# IOIO.net
KiCad netlist of a schematic drawn in EAGLE
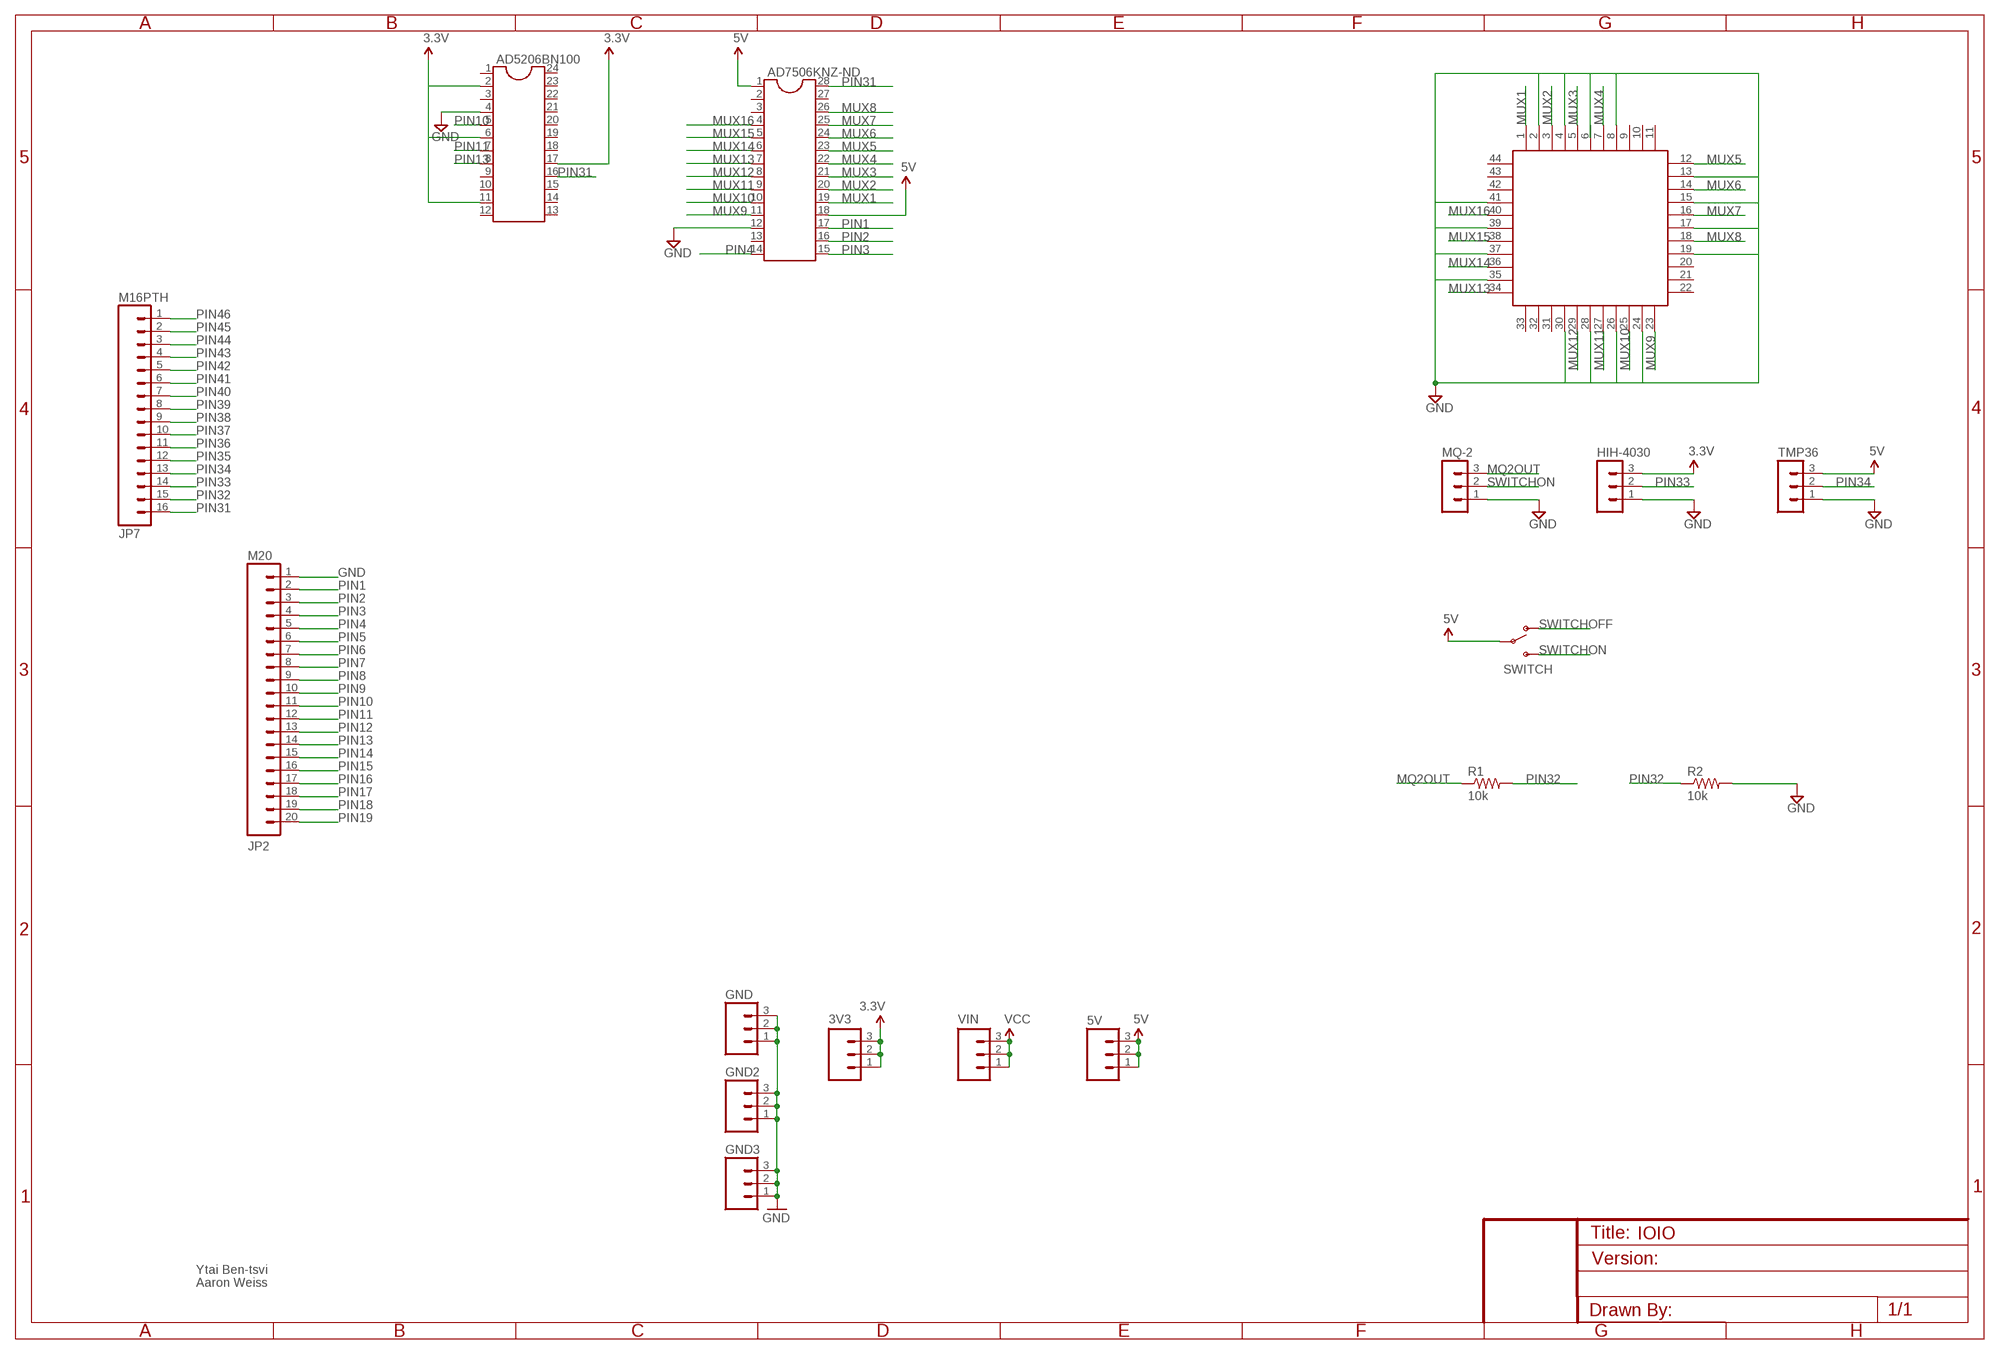
[diagram p0: schematic, sheet 1]

(export (version "E")
  (design (tool "Eeschema 10.0.6"))
  (components
    (comp (ref "3V3")
      (value "M03PTH")
      (footprint "eagle-import:1X03")
      (libsource (lib "eagle-import") (part "M03PTH"))
    )
    (comp (ref "5V")
      (value "M03PTH")
      (footprint "eagle-import:1X03")
      (libsource (lib "eagle-import") (part "M03PTH"))
    )
    (comp (ref "AD5206BN100")
      (value "DIL24-3")
      (footprint "eagle-import:DIL24-3")
      (libsource (lib "eagle-import") (part "DIL24-3"))
    )
    (comp (ref "AD7506KNZ-ND")
      (value "DIL28")
      (footprint "eagle-import:DIL28-6")
      (libsource (lib "eagle-import") (part "DIL28"))
    )
    (comp (ref "GND")
      (value "M03PTH")
      (footprint "eagle-import:1X03")
      (libsource (lib "eagle-import") (part "M03PTH"))
    )
    (comp (ref "GND2")
      (value "M03PTH")
      (footprint "eagle-import:1X03")
      (libsource (lib "eagle-import") (part "M03PTH"))
    )
    (comp (ref "GND3")
      (value "M03PTH")
      (footprint "eagle-import:1X03")
      (libsource (lib "eagle-import") (part "M03PTH"))
    )
    (comp (ref "HIH-4030")
      (value "MA03-1")
      (footprint "eagle-import:MA03-1")
      (libsource (lib "eagle-import") (part "MA03-1"))
    )
    (comp (ref "JP2")
      (value "M20")
      (footprint "eagle-import:1X20")
      (libsource (lib "eagle-import") (part "M20"))
    )
    (comp (ref "JP7")
      (value "M16PTH")
      (footprint "eagle-import:1X16")
      (libsource (lib "eagle-import") (part "M16PTH"))
    )
    (comp (ref "MQ-2")
      (value "MA03-1")
      (footprint "eagle-import:MA03-1")
      (libsource (lib "eagle-import") (part "MA03-1"))
    )
    (comp (ref "R1")
      (value "10k")
      (footprint "eagle-import:0207_7")
      (libsource (lib "eagle-import") (part "R-US_0207/7"))
    )
    (comp (ref "R2")
      (value "10k")
      (footprint "eagle-import:0207_7")
      (libsource (lib "eagle-import") (part "R-US_0207/7"))
    )
    (comp (ref "SWITCH")
      (value "SWITCH-SPSTPTH")
      (footprint "eagle-import:SWITCH-SPDT")
      (libsource (lib "eagle-import") (part "SWITCH-SPSTPTH"))
    )
    (comp (ref "TMP36")
      (value "MA03-1")
      (footprint "eagle-import:MA03-1")
      (libsource (lib "eagle-import") (part "MA03-1"))
    )
    (comp (ref "U$1")
      (value "S44")
      (footprint "eagle-import:S44")
      (libsource (lib "eagle-import") (part "S44"))
    )
    (comp (ref "VIN")
      (value "M03PTH")
      (footprint "eagle-import:1X03")
      (libsource (lib "eagle-import") (part "M03PTH"))
    )
  )
  (nets
    (net (code "1") (name "/MQ2OUT") (class "Default")
      (node (ref "MQ-2") (pin "3") (pinfunction "3_3") (pintype "passive"))
      (node (ref "R1") (pin "1") (pinfunction "1_1") (pintype "passive"))
    )
    (net (code "2") (name "/MUX1") (class "Default")
      (node (ref "AD7506KNZ-ND") (pin "19") (pinfunction "19_19") (pintype "passive"))
      (node (ref "U$1") (pin "1") (pinfunction "P$1_1") (pintype "bidirectional"))
    )
    (net (code "3") (name "/MUX2") (class "Default")
      (node (ref "AD7506KNZ-ND") (pin "20") (pinfunction "20_20") (pintype "passive"))
      (node (ref "U$1") (pin "3") (pinfunction "P$3_3") (pintype "bidirectional"))
    )
    (net (code "4") (name "/MUX3") (class "Default")
      (node (ref "AD7506KNZ-ND") (pin "21") (pinfunction "21_21") (pintype "passive"))
      (node (ref "U$1") (pin "5") (pinfunction "P$5_5") (pintype "bidirectional"))
    )
    (net (code "5") (name "/MUX4") (class "Default")
      (node (ref "AD7506KNZ-ND") (pin "22") (pinfunction "22_22") (pintype "passive"))
      (node (ref "U$1") (pin "7") (pinfunction "P$7_7") (pintype "bidirectional"))
    )
    (net (code "6") (name "/MUX5") (class "Default")
      (node (ref "AD7506KNZ-ND") (pin "23") (pinfunction "23_23") (pintype "passive"))
      (node (ref "U$1") (pin "12") (pinfunction "P$12_12") (pintype "bidirectional"))
    )
    (net (code "7") (name "/MUX6") (class "Default")
      (node (ref "AD7506KNZ-ND") (pin "24") (pinfunction "24_24") (pintype "passive"))
      (node (ref "U$1") (pin "14") (pinfunction "P$14_14") (pintype "bidirectional"))
    )
    (net (code "8") (name "/MUX7") (class "Default")
      (node (ref "AD7506KNZ-ND") (pin "25") (pinfunction "25_25") (pintype "passive"))
      (node (ref "U$1") (pin "16") (pinfunction "P$16_16") (pintype "bidirectional"))
    )
    (net (code "9") (name "/MUX8") (class "Default")
      (node (ref "AD7506KNZ-ND") (pin "26") (pinfunction "26_26") (pintype "passive"))
      (node (ref "U$1") (pin "18") (pinfunction "P$18_18") (pintype "bidirectional"))
    )
    (net (code "10") (name "/MUX9") (class "Default")
      (node (ref "AD7506KNZ-ND") (pin "11") (pinfunction "11_11") (pintype "passive"))
      (node (ref "U$1") (pin "23") (pinfunction "P$23_23") (pintype "bidirectional"))
    )
    (net (code "11") (name "/MUX10") (class "Default")
      (node (ref "AD7506KNZ-ND") (pin "10") (pinfunction "10_10") (pintype "passive"))
      (node (ref "U$1") (pin "25") (pinfunction "P$25_25") (pintype "bidirectional"))
    )
    (net (code "12") (name "/MUX11") (class "Default")
      (node (ref "AD7506KNZ-ND") (pin "9") (pinfunction "9_9") (pintype "passive"))
      (node (ref "U$1") (pin "27") (pinfunction "P$27_27") (pintype "bidirectional"))
    )
    (net (code "13") (name "/MUX12") (class "Default")
      (node (ref "AD7506KNZ-ND") (pin "8") (pinfunction "8_8") (pintype "passive"))
      (node (ref "U$1") (pin "29") (pinfunction "P$29_29") (pintype "bidirectional"))
    )
    (net (code "14") (name "/MUX13") (class "Default")
      (node (ref "AD7506KNZ-ND") (pin "7") (pinfunction "7_7") (pintype "passive"))
      (node (ref "U$1") (pin "34") (pinfunction "P$34_34") (pintype "bidirectional"))
    )
    (net (code "15") (name "/MUX14") (class "Default")
      (node (ref "AD7506KNZ-ND") (pin "6") (pinfunction "6_6") (pintype "passive"))
      (node (ref "U$1") (pin "36") (pinfunction "P$36_36") (pintype "bidirectional"))
    )
    (net (code "16") (name "/MUX15") (class "Default")
      (node (ref "AD7506KNZ-ND") (pin "5") (pinfunction "5_5") (pintype "passive"))
      (node (ref "U$1") (pin "38") (pinfunction "P$38_38") (pintype "bidirectional"))
    )
    (net (code "17") (name "/MUX16") (class "Default")
      (node (ref "AD7506KNZ-ND") (pin "4") (pinfunction "4_4") (pintype "passive"))
      (node (ref "U$1") (pin "40") (pinfunction "P$40_40") (pintype "bidirectional"))
    )
    (net (code "18") (name "/PIN1") (class "Default")
      (node (ref "AD7506KNZ-ND") (pin "17") (pinfunction "17_17") (pintype "passive"))
      (node (ref "JP2") (pin "2") (pinfunction "2_2") (pintype "passive"))
    )
    (net (code "19") (name "/PIN2") (class "Default")
      (node (ref "AD7506KNZ-ND") (pin "16") (pinfunction "16_16") (pintype "passive"))
      (node (ref "JP2") (pin "3") (pinfunction "3_3") (pintype "passive"))
    )
    (net (code "20") (name "/PIN3") (class "Default")
      (node (ref "AD7506KNZ-ND") (pin "15") (pinfunction "15_15") (pintype "passive"))
      (node (ref "JP2") (pin "4") (pinfunction "4_4") (pintype "passive"))
    )
    (net (code "21") (name "/PIN4") (class "Default")
      (node (ref "AD7506KNZ-ND") (pin "14") (pinfunction "14_14") (pintype "passive"))
      (node (ref "JP2") (pin "5") (pinfunction "5_5") (pintype "passive"))
    )
    (net (code "22") (name "/PIN5") (class "Default")
      (node (ref "JP2") (pin "6") (pinfunction "6_6") (pintype "passive"))
    )
    (net (code "23") (name "/PIN6") (class "Default")
      (node (ref "JP2") (pin "7") (pinfunction "7_7") (pintype "passive"))
    )
    (net (code "24") (name "/PIN7") (class "Default")
      (node (ref "JP2") (pin "8") (pinfunction "8_8") (pintype "passive"))
    )
    (net (code "25") (name "/PIN8") (class "Default")
      (node (ref "JP2") (pin "9") (pinfunction "9_9") (pintype "passive"))
    )
    (net (code "26") (name "/PIN9") (class "Default")
      (node (ref "JP2") (pin "10") (pinfunction "10_10") (pintype "passive"))
    )
    (net (code "27") (name "/PIN10") (class "Default")
      (node (ref "AD5206BN100") (pin "5") (pinfunction "5_5") (pintype "passive"))
      (node (ref "JP2") (pin "11") (pinfunction "11_11") (pintype "passive"))
    )
    (net (code "28") (name "/PIN11") (class "Default")
      (node (ref "AD5206BN100") (pin "7") (pinfunction "7_7") (pintype "passive"))
      (node (ref "JP2") (pin "12") (pinfunction "12_12") (pintype "passive"))
    )
    (net (code "29") (name "/PIN12") (class "Default")
      (node (ref "JP2") (pin "13") (pinfunction "13_13") (pintype "passive"))
    )
    (net (code "30") (name "/PIN13") (class "Default")
      (node (ref "AD5206BN100") (pin "8") (pinfunction "8_8") (pintype "passive"))
      (node (ref "JP2") (pin "14") (pinfunction "14_14") (pintype "passive"))
    )
    (net (code "31") (name "/PIN14") (class "Default")
      (node (ref "JP2") (pin "15") (pinfunction "15_15") (pintype "passive"))
    )
    (net (code "32") (name "/PIN15") (class "Default")
      (node (ref "JP2") (pin "16") (pinfunction "16_16") (pintype "passive"))
    )
    (net (code "33") (name "/PIN16") (class "Default")
      (node (ref "JP2") (pin "17") (pinfunction "17_17") (pintype "passive"))
    )
    (net (code "34") (name "/PIN17") (class "Default")
      (node (ref "JP2") (pin "18") (pinfunction "18_18") (pintype "passive"))
    )
    (net (code "35") (name "/PIN18") (class "Default")
      (node (ref "JP2") (pin "19") (pinfunction "19_19") (pintype "passive"))
    )
    (net (code "36") (name "/PIN19") (class "Default")
      (node (ref "JP2") (pin "20") (pinfunction "20_20") (pintype "passive"))
    )
    (net (code "37") (name "/PIN31") (class "Default")
      (node (ref "AD5206BN100") (pin "16") (pinfunction "16_16") (pintype "passive"))
      (node (ref "AD7506KNZ-ND") (pin "28") (pinfunction "28_28") (pintype "passive"))
      (node (ref "JP7") (pin "16") (pinfunction "16_16") (pintype "passive"))
    )
    (net (code "38") (name "/PIN32") (class "Default")
      (node (ref "JP7") (pin "15") (pinfunction "15_15") (pintype "passive"))
      (node (ref "R1") (pin "2") (pinfunction "2_2") (pintype "passive"))
      (node (ref "R2") (pin "1") (pinfunction "1_1") (pintype "passive"))
    )
    (net (code "39") (name "/PIN33") (class "Default")
      (node (ref "HIH-4030") (pin "2") (pinfunction "2_2") (pintype "passive"))
      (node (ref "JP7") (pin "14") (pinfunction "14_14") (pintype "passive"))
    )
    (net (code "40") (name "/PIN34") (class "Default")
      (node (ref "JP7") (pin "13") (pinfunction "13_13") (pintype "passive"))
      (node (ref "TMP36") (pin "2") (pinfunction "2_2") (pintype "passive"))
    )
    (net (code "41") (name "/PIN35") (class "Default")
      (node (ref "JP7") (pin "12") (pinfunction "12_12") (pintype "passive"))
    )
    (net (code "42") (name "/PIN36") (class "Default")
      (node (ref "JP7") (pin "11") (pinfunction "11_11") (pintype "passive"))
    )
    (net (code "43") (name "/PIN37") (class "Default")
      (node (ref "JP7") (pin "10") (pinfunction "10_10") (pintype "passive"))
    )
    (net (code "44") (name "/PIN38") (class "Default")
      (node (ref "JP7") (pin "9") (pinfunction "9_9") (pintype "passive"))
    )
    (net (code "45") (name "/PIN39") (class "Default")
      (node (ref "JP7") (pin "8") (pinfunction "8_8") (pintype "passive"))
    )
    (net (code "46") (name "/PIN40") (class "Default")
      (node (ref "JP7") (pin "7") (pinfunction "7_7") (pintype "passive"))
    )
    (net (code "47") (name "/PIN41") (class "Default")
      (node (ref "JP7") (pin "6") (pinfunction "6_6") (pintype "passive"))
    )
    (net (code "48") (name "/PIN42") (class "Default")
      (node (ref "JP7") (pin "5") (pinfunction "5_5") (pintype "passive"))
    )
    (net (code "49") (name "/PIN43") (class "Default")
      (node (ref "JP7") (pin "4") (pinfunction "4_4") (pintype "passive"))
    )
    (net (code "50") (name "/PIN44") (class "Default")
      (node (ref "JP7") (pin "3") (pinfunction "3_3") (pintype "passive"))
    )
    (net (code "51") (name "/PIN45") (class "Default")
      (node (ref "JP7") (pin "2") (pinfunction "2_2") (pintype "passive"))
    )
    (net (code "52") (name "/PIN46") (class "Default")
      (node (ref "JP7") (pin "1") (pinfunction "1_1") (pintype "passive"))
    )
    (net (code "53") (name "/SWITCHOFF") (class "Default")
      (node (ref "SWITCH") (pin "1") (pinfunction "O_1") (pintype "passive"))
    )
    (net (code "54") (name "/SWITCHON") (class "Default")
      (node (ref "MQ-2") (pin "2") (pinfunction "2_2") (pintype "passive"))
      (node (ref "SWITCH") (pin "3") (pinfunction "S_3") (pintype "passive"))
    )
    (net (code "55") (name "3.3V") (class "Default")
      (node (ref "3V3") (pin "1") (pinfunction "1_1") (pintype "passive"))
      (node (ref "3V3") (pin "2") (pinfunction "2_2") (pintype "passive"))
      (node (ref "3V3") (pin "3") (pinfunction "3_3") (pintype "passive"))
      (node (ref "AD5206BN100") (pin "11") (pinfunction "11_11") (pintype "passive"))
      (node (ref "AD5206BN100") (pin "17") (pinfunction "17_17") (pintype "passive"))
      (node (ref "AD5206BN100") (pin "2") (pinfunction "2_2") (pintype "passive"))
      (node (ref "AD5206BN100") (pin "6") (pinfunction "6_6") (pintype "passive"))
      (node (ref "HIH-4030") (pin "3") (pinfunction "3_3") (pintype "passive"))
    )
    (net (code "56") (name "5V") (class "Default")
      (node (ref "5V") (pin "1") (pinfunction "1_1") (pintype "passive"))
      (node (ref "5V") (pin "2") (pinfunction "2_2") (pintype "passive"))
      (node (ref "5V") (pin "3") (pinfunction "3_3") (pintype "passive"))
      (node (ref "AD7506KNZ-ND") (pin "1") (pinfunction "1_1") (pintype "passive"))
      (node (ref "AD7506KNZ-ND") (pin "18") (pinfunction "18_18") (pintype "passive"))
      (node (ref "SWITCH") (pin "2") (pinfunction "P_2") (pintype "passive"))
      (node (ref "TMP36") (pin "3") (pinfunction "3_3") (pintype "passive"))
    )
    (net (code "57") (name "GND") (class "Default")
      (node (ref "AD5206BN100") (pin "4") (pinfunction "4_4") (pintype "passive"))
      (node (ref "AD7506KNZ-ND") (pin "12") (pinfunction "12_12") (pintype "passive"))
      (node (ref "GND") (pin "1") (pinfunction "1_1") (pintype "passive"))
      (node (ref "GND") (pin "2") (pinfunction "2_2") (pintype "passive"))
      (node (ref "GND") (pin "3") (pinfunction "3_3") (pintype "passive"))
      (node (ref "GND2") (pin "1") (pinfunction "1_1") (pintype "passive"))
      (node (ref "GND2") (pin "2") (pinfunction "2_2") (pintype "passive"))
      (node (ref "GND2") (pin "3") (pinfunction "3_3") (pintype "passive"))
      (node (ref "GND3") (pin "1") (pinfunction "1_1") (pintype "passive"))
      (node (ref "GND3") (pin "2") (pinfunction "2_2") (pintype "passive"))
      (node (ref "GND3") (pin "3") (pinfunction "3_3") (pintype "passive"))
      (node (ref "HIH-4030") (pin "1") (pinfunction "1_1") (pintype "passive"))
      (node (ref "JP2") (pin "1") (pinfunction "1_1") (pintype "passive"))
      (node (ref "MQ-2") (pin "1") (pinfunction "1_1") (pintype "passive"))
      (node (ref "R2") (pin "2") (pinfunction "2_2") (pintype "passive"))
      (node (ref "TMP36") (pin "1") (pinfunction "1_1") (pintype "passive"))
      (node (ref "U$1") (pin "13") (pinfunction "P$13_13") (pintype "bidirectional"))
      (node (ref "U$1") (pin "15") (pinfunction "P$15_15") (pintype "bidirectional"))
      (node (ref "U$1") (pin "17") (pinfunction "P$17_17") (pintype "bidirectional"))
      (node (ref "U$1") (pin "19") (pinfunction "P$19_19") (pintype "bidirectional"))
      (node (ref "U$1") (pin "2") (pinfunction "P$2_2") (pintype "bidirectional"))
      (node (ref "U$1") (pin "24") (pinfunction "P$24_24") (pintype "bidirectional"))
      (node (ref "U$1") (pin "26") (pinfunction "P$26_26") (pintype "bidirectional"))
      (node (ref "U$1") (pin "28") (pinfunction "P$28_28") (pintype "bidirectional"))
      (node (ref "U$1") (pin "30") (pinfunction "P$30_30") (pintype "bidirectional"))
      (node (ref "U$1") (pin "35") (pinfunction "P$35_35") (pintype "bidirectional"))
      (node (ref "U$1") (pin "37") (pinfunction "P$37_37") (pintype "bidirectional"))
      (node (ref "U$1") (pin "39") (pinfunction "P$39_39") (pintype "bidirectional"))
      (node (ref "U$1") (pin "4") (pinfunction "P$4_4") (pintype "bidirectional"))
      (node (ref "U$1") (pin "41") (pinfunction "P$41_41") (pintype "bidirectional"))
      (node (ref "U$1") (pin "8") (pinfunction "P$8_8") (pintype "bidirectional"))
    )
    (net (code "58") (name "VCC") (class "Default")
      (node (ref "VIN") (pin "1") (pinfunction "1_1") (pintype "passive"))
      (node (ref "VIN") (pin "2") (pinfunction "2_2") (pintype "passive"))
      (node (ref "VIN") (pin "3") (pinfunction "3_3") (pintype "passive"))
    )
    (net (code "59") (name "unconnected-(AD5206BN100-Pad1)") (class "Default")
      (node (ref "AD5206BN100") (pin "1") (pinfunction "1_1") (pintype "passive"))
    )
    (net (code "60") (name "unconnected-(AD5206BN100-Pad3)") (class "Default")
      (node (ref "AD5206BN100") (pin "3") (pinfunction "3_3") (pintype "passive"))
    )
    (net (code "61") (name "unconnected-(AD5206BN100-Pad9)") (class "Default")
      (node (ref "AD5206BN100") (pin "9") (pinfunction "9_9") (pintype "passive"))
    )
    (net (code "62") (name "unconnected-(AD5206BN100-Pad10)") (class "Default")
      (node (ref "AD5206BN100") (pin "10") (pinfunction "10_10") (pintype "passive"))
    )
    (net (code "63") (name "unconnected-(AD5206BN100-Pad12)") (class "Default")
      (node (ref "AD5206BN100") (pin "12") (pinfunction "12_12") (pintype "passive"))
    )
    (net (code "64") (name "unconnected-(AD5206BN100-Pad13)") (class "Default")
      (node (ref "AD5206BN100") (pin "13") (pinfunction "13_13") (pintype "passive"))
    )
    (net (code "65") (name "unconnected-(AD5206BN100-Pad14)") (class "Default")
      (node (ref "AD5206BN100") (pin "14") (pinfunction "14_14") (pintype "passive"))
    )
    (net (code "66") (name "unconnected-(AD5206BN100-Pad15)") (class "Default")
      (node (ref "AD5206BN100") (pin "15") (pinfunction "15_15") (pintype "passive"))
    )
    (net (code "67") (name "unconnected-(AD5206BN100-Pad18)") (class "Default")
      (node (ref "AD5206BN100") (pin "18") (pinfunction "18_18") (pintype "passive"))
    )
    (net (code "68") (name "unconnected-(AD5206BN100-Pad19)") (class "Default")
      (node (ref "AD5206BN100") (pin "19") (pinfunction "19_19") (pintype "passive"))
    )
    (net (code "69") (name "unconnected-(AD5206BN100-Pad20)") (class "Default")
      (node (ref "AD5206BN100") (pin "20") (pinfunction "20_20") (pintype "passive"))
    )
    (net (code "70") (name "unconnected-(AD5206BN100-Pad21)") (class "Default")
      (node (ref "AD5206BN100") (pin "21") (pinfunction "21_21") (pintype "passive"))
    )
    (net (code "71") (name "unconnected-(AD5206BN100-Pad22)") (class "Default")
      (node (ref "AD5206BN100") (pin "22") (pinfunction "22_22") (pintype "passive"))
    )
    (net (code "72") (name "unconnected-(AD5206BN100-Pad23)") (class "Default")
      (node (ref "AD5206BN100") (pin "23") (pinfunction "23_23") (pintype "passive"))
    )
    (net (code "73") (name "unconnected-(AD5206BN100-Pad24)") (class "Default")
      (node (ref "AD5206BN100") (pin "24") (pinfunction "24_24") (pintype "passive"))
    )
    (net (code "74") (name "unconnected-(AD7506KNZ-ND-Pad2)") (class "Default")
      (node (ref "AD7506KNZ-ND") (pin "2") (pinfunction "2_2") (pintype "passive"))
    )
    (net (code "75") (name "unconnected-(AD7506KNZ-ND-Pad3)") (class "Default")
      (node (ref "AD7506KNZ-ND") (pin "3") (pinfunction "3_3") (pintype "passive"))
    )
    (net (code "76") (name "unconnected-(AD7506KNZ-ND-Pad13)") (class "Default")
      (node (ref "AD7506KNZ-ND") (pin "13") (pinfunction "13_13") (pintype "passive"))
    )
    (net (code "77") (name "unconnected-(AD7506KNZ-ND-Pad27)") (class "Default")
      (node (ref "AD7506KNZ-ND") (pin "27") (pinfunction "27_27") (pintype "passive"))
    )
    (net (code "78") (name "unconnected-(U$1-P$6-Pad6)") (class "Default")
      (node (ref "U$1") (pin "6") (pinfunction "P$6_6") (pintype "bidirectional"))
    )
    (net (code "79") (name "unconnected-(U$1-P$9-Pad9)") (class "Default")
      (node (ref "U$1") (pin "9") (pinfunction "P$9_9") (pintype "bidirectional"))
    )
    (net (code "80") (name "unconnected-(U$1-P$10-Pad10)") (class "Default")
      (node (ref "U$1") (pin "10") (pinfunction "P$10_10") (pintype "bidirectional"))
    )
    (net (code "81") (name "unconnected-(U$1-P$11-Pad11)") (class "Default")
      (node (ref "U$1") (pin "11") (pinfunction "P$11_11") (pintype "bidirectional"))
    )
    (net (code "82") (name "unconnected-(U$1-P$20-Pad20)") (class "Default")
      (node (ref "U$1") (pin "20") (pinfunction "P$20_20") (pintype "bidirectional"))
    )
    (net (code "83") (name "unconnected-(U$1-P$21-Pad21)") (class "Default")
      (node (ref "U$1") (pin "21") (pinfunction "P$21_21") (pintype "bidirectional"))
    )
    (net (code "84") (name "unconnected-(U$1-P$22-Pad22)") (class "Default")
      (node (ref "U$1") (pin "22") (pinfunction "P$22_22") (pintype "bidirectional"))
    )
    (net (code "85") (name "unconnected-(U$1-P$31-Pad31)") (class "Default")
      (node (ref "U$1") (pin "31") (pinfunction "P$31_31") (pintype "bidirectional"))
    )
    (net (code "86") (name "unconnected-(U$1-P$32-Pad32)") (class "Default")
      (node (ref "U$1") (pin "32") (pinfunction "P$32_32") (pintype "bidirectional"))
    )
    (net (code "87") (name "unconnected-(U$1-P$33-Pad33)") (class "Default")
      (node (ref "U$1") (pin "33") (pinfunction "P$33_33") (pintype "bidirectional"))
    )
    (net (code "88") (name "unconnected-(U$1-P$42-Pad42)") (class "Default")
      (node (ref "U$1") (pin "42") (pinfunction "P$42_42") (pintype "bidirectional"))
    )
    (net (code "89") (name "unconnected-(U$1-P$43-Pad43)") (class "Default")
      (node (ref "U$1") (pin "43") (pinfunction "P$43_43") (pintype "bidirectional"))
    )
    (net (code "90") (name "unconnected-(U$1-P$44-Pad44)") (class "Default")
      (node (ref "U$1") (pin "44") (pinfunction "P$44_44") (pintype "bidirectional"))
    )
  )
)
